# TPS6513x.net
KiCad netlist of a schematic drawn in Altium Designer
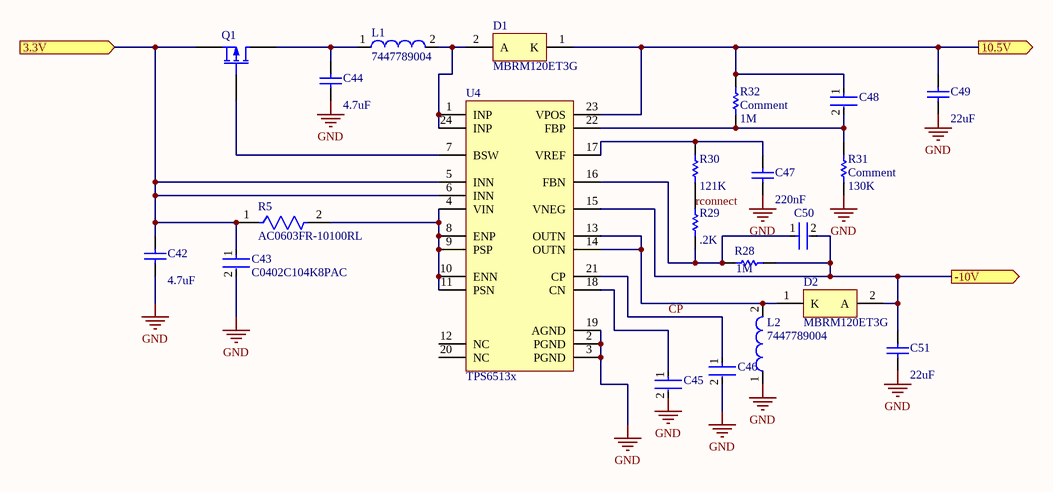
[diagram p0: TPS6513x.SchDoc]

(export (version "E")
  (design (tool "Eeschema 10.0.6"))
  (components
    (comp (ref "C42")
      (value "4.7uF")
      (footprint "4.7uF_C1206C475K3RACAUTO")
      (description "Capacitor")
      (fields (field (name "Comment") "Comment") (field (name "PUBLISHER") "Altium Limited"))
      (libsource (lib "Miscellaneous Devices") (part "Cap"))
    )
    (comp (ref "C43")
      (value "C0402C104K8PAC")
      (footprint "FP-C0402-BB-MFG")
      (description "C0402 0.10 μF X5R 10.00% 10 V")
      (fields
        (field (name "MANUFACTURER") "Kemet")
        (field (name "OCTOPART") "https://octopart.com/c0402c104k8pac-kemet-2645080")
      )
      (libsource (lib "Altium Content Vault") (part "b4654b650e69147ec39a6b967a45e02"))
    )
    (comp (ref "C44")
      (value "4.7uF")
      (footprint "4.7uF_C1206C475K3RACAUTO")
      (description "Capacitor")
      (fields (field (name "Comment") "Comment") (field (name "PUBLISHER") "Altium Limited"))
      (libsource (lib "Miscellaneous Devices") (part "Cap"))
    )
    (comp (ref "C45")
      (value "C1206C472J5GAC")
      (footprint "FP-C1206C-EB-MFG")
      (description "C1206 4,700 pF C0G 5.00% 50 V")
      (fields
        (field (name "OCTOPART") "https://octopart.com/c1206c472j5gac-kemet-1350327")
        (field (name "MANUFACTURER") "KEMET")
      )
      (libsource (lib "Altium Content Vault") (part "b4654b650e69147ec39a6b967a45e02"))
    )
    (comp (ref "C46")
      (value "C0402C103J4RAC")
      (footprint "FP-C0402-BB-MFG")
      (description "C0402 10,000 pF X7R 5.00% 16 V")
      (fields
        (field (name "TOLERANCE") "0.05")
        (field (name "OCTOPART") "https://octopart.com/c0402c103j4rac-kemet-8293494")
      )
      (libsource (lib "Altium Content Vault") (part "b4654b650e69147ec39a6b967a45e02"))
    )
    (comp (ref "C47")
      (value "220nF")
      (footprint "PCBComponent_1")
      (description "Capacitor")
      (fields (field (name "Comment") "Comment") (field (name "PUBLISHER") "Altium Limited"))
      (libsource (lib "Miscellaneous Devices") (part "Cap"))
    )
    (comp (ref "C48")
      (value "CGA1A2C0G1E6R8D030BA")
      (footprint "FP-CGA1A-0_1-0_03-IPC_B")
      (description "Cap Ceramic 6.8pF 25V C0G 0.5pF Pad SMD 0201 125°C Automotive T/R")
      (libsource (lib "Altium Content Vault") (part "b4654b650e69147ec39a6b967a45e02"))
    )
    (comp (ref "C49")
      (value "22uF")
      (footprint "Cap22uF_C1206C226M4PAC7800")
      (description "Capacitor")
      (fields (field (name "Comment") "Comment") (field (name "PUBLISHER") "Altium Limited"))
      (libsource (lib "Miscellaneous Devices") (part "Cap"))
    )
    (comp (ref "C50")
      (value "C0805C759D5GACTU")
      (footprint "FP-C0805C-DN-MFG")
      (description "CAP CER 7.5PF 50V NP0 0805")
      (fields (field (name "MANUFACTURER") "KEMET") (field (name "TOLERANCE") "0.5 pF"))
      (libsource (lib "Altium Content Vault") (part "b4654b650e69147ec39a6b967a45e02"))
    )
    (comp (ref "C51")
      (value "22uF")
      (footprint "Cap22uF_C1206C226M4PAC7800")
      (description "Capacitor")
      (fields (field (name "Comment") "Comment") (field (name "PUBLISHER") "Altium Limited"))
      (libsource (lib "Miscellaneous Devices") (part "Cap"))
    )
    (comp (ref "D1")
      (value "MBRM120ET3G")
      (footprint "ONSC-POWERMITE-2-457-04_D_V")
      (description "Schottky Power Rectifier, 2-Pin Powermite, Pb-Free, Tape and Reel")
      (fields (field (name "MANUFACTURER") "On Semiconductor"))
      (libsource (lib "") (part "ONSC-D-K1A2-2_A_1"))
    )
    (comp (ref "D2")
      (value "MBRM120ET3G")
      (footprint "ONSC-POWERMITE-2-457-04_D_V")
      (description "Schottky Power Rectifier, 2-Pin Powermite, Pb-Free, Tape and Reel")
      (fields (field (name "MANUFACTURER") "On Semiconductor"))
      (libsource (lib "Altium Content Vault") (part "ONSC-D-K1A2-2_A"))
    )
    (comp (ref "L1")
      (value "7447789004")
      (footprint "WE-PD-S-PB")
      (description "SMD-Shielded Power Inductor WE-PD, L=4.70 µH")
      (fields (field (name "MANUFACTURER") "Wuerth Elektronik"))
      (libsource (lib "Altium Content Vault") (part "PAS-IND-INDUCTOR-2"))
    )
    (comp (ref "L2")
      (value "7447789004")
      (footprint "WE-PD-S-PB")
      (description "SMD-Shielded Power Inductor WE-PD, L=4.70 µH")
      (fields (field (name "MANUFACTURER") "Wuerth Elektronik"))
      (libsource (lib "Altium Content Vault") (part "PAS-IND-INDUCTOR-2"))
    )
    (comp (ref "Q1")
      (value "Comment")
      (footprint "PCBComponent_1")
      (description "P-Channel MOSFET")
      (fields (field (name "PUBLISHER") "Altium Limited"))
      (libsource (lib "Miscellaneous Devices") (part "MOSFET-P"))
    )
    (comp (ref "R5")
      (value "AC0603FR-10100RL")
      (footprint "FP-AC0603-IPC_A")
      (description "RES 100Ω 1.00% 0.1W 0603")
      (fields (field (name "TOLERANCE") "1%"))
      (libsource (lib "Altium Content Vault") (part "1029c3af85768c4190bb7ad29bc67b5"))
    )
    (comp (ref "R28")
      (value "1M")
      (footprint "1Mohm_ESR01MZPF1004")
      (description "Resistor")
      (fields (field (name "Comment") "Comment") (field (name "PUBLISHER") "Altium Limited"))
      (libsource (lib "Miscellaneous Devices") (part "Res1"))
    )
    (comp (ref "R29")
      (value ".2K")
      (footprint "200ohm_ESR01MZPF2000")
      (description "Resistor")
      (fields (field (name "Comment") "Comment") (field (name "PUBLISHER") "Altium Limited"))
      (libsource (lib "Miscellaneous Devices") (part "Res1"))
    )
    (comp (ref "R30")
      (value "121K")
      (footprint "121k_RE0201BRE07121KL")
      (description "Resistor")
      (fields (field (name "Comment") "Comment") (field (name "PUBLISHER") "Altium Limited"))
      (libsource (lib "Miscellaneous Devices") (part "Res1"))
    )
    (comp (ref "R31")
      (value "Comment")
      (footprint "130k_RGV3216P-1303-B-T1")
      (description "Resistor")
      (fields (field (name "ALTIUM_VALUE") "130K") (field (name "PUBLISHER") "Altium Limited"))
      (libsource (lib "Miscellaneous Devices") (part "Res1"))
    )
    (comp (ref "R32")
      (value "Comment")
      (footprint "1Mohm_ESR01MZPF1004")
      (description "Resistor")
      (fields (field (name "ALTIUM_VALUE") "1M") (field (name "PUBLISHER") "Altium Limited"))
      (libsource (lib "Miscellaneous Devices") (part "Res1"))
    )
    (comp (ref "U4")
      (value "TPS6513x")
      (footprint "RGE0024B_V")
      (fields (field (name "PARTNUMBER") "TPS65130RGER") (field (name "MANUFACTURER") "Texas Instruments"))
      (libsource (lib "Altium Content Vault") (part "TI-TPS65130RGE24-2450X2450TP"))
    )
  )
  (nets
    (net (code "1") (name "/-10V") (class "Default")
      (node (ref "C50") (pin "2") (pinfunction "2_2") (pintype "passive"))
      (node (ref "C51") (pin "2") (pinfunction "2_2") (pintype "passive"))
      (node (ref "D2") (pin "2") (pinfunction "A_2") (pintype "passive"))
      (node (ref "R28") (pin "1") (pinfunction "1_1") (pintype "passive"))
      (node (ref "U4") (pin "15") (pinfunction "VNEG_15") (pintype "passive"))
    )
    (net (code "2") (name "/3.3V") (class "Default")
      (node (ref "C42") (pin "1") (pinfunction "1_1") (pintype "passive"))
      (node (ref "C43") (pin "1") (pinfunction "1_1") (pintype "passive"))
      (node (ref "Q1") (pin "3") (pinfunction "S_3") (pintype "passive"))
      (node (ref "R5") (pin "1") (pinfunction "1_1") (pintype "passive"))
      (node (ref "U4") (pin "5") (pinfunction "INN_5") (pintype "passive"))
      (node (ref "U4") (pin "6") (pinfunction "INN_6") (pintype "passive"))
    )
    (net (code "3") (name "/10.5V") (class "Default")
      (node (ref "C48") (pin "1") (pinfunction "1_1") (pintype "passive"))
      (node (ref "C49") (pin "2") (pinfunction "2_2") (pintype "passive"))
      (node (ref "D1") (pin "1") (pinfunction "K_1") (pintype "passive"))
      (node (ref "R32") (pin "2") (pinfunction "2_2") (pintype "passive"))
      (node (ref "U4") (pin "23") (pinfunction "VPOS_23") (pintype "passive"))
    )
    (net (code "4") (name "/CP") (class "Default")
      (node (ref "C46") (pin "1") (pinfunction "1_1") (pintype "passive"))
      (node (ref "U4") (pin "21") (pinfunction "CP_21") (pintype "passive"))
    )
    (net (code "6") (name "GND") (class "Default")
      (node (ref "C42") (pin "2") (pinfunction "2_2") (pintype "passive"))
      (node (ref "C43") (pin "2") (pinfunction "2_2") (pintype "passive"))
      (node (ref "C44") (pin "2") (pinfunction "2_2") (pintype "passive"))
      (node (ref "C45") (pin "2") (pinfunction "2_2") (pintype "passive"))
      (node (ref "C46") (pin "2") (pinfunction "2_2") (pintype "passive"))
      (node (ref "C47") (pin "1") (pinfunction "1_1") (pintype "passive"))
      (node (ref "C49") (pin "1") (pinfunction "1_1") (pintype "passive"))
      (node (ref "C51") (pin "1") (pinfunction "1_1") (pintype "passive"))
      (node (ref "L2") (pin "1") (pinfunction "1_1") (pintype "passive"))
      (node (ref "R31") (pin "1") (pinfunction "1_1") (pintype "passive"))
      (node (ref "U4") (pin "19") (pinfunction "AGND_19") (pintype "passive"))
      (node (ref "U4") (pin "2") (pinfunction "PGND_2") (pintype "passive"))
      (node (ref "U4") (pin "3") (pinfunction "PGND_3") (pintype "passive"))
    )
    (net (code "7") (name "Net-(D1-A)") (class "Default")
      (node (ref "D1") (pin "2") (pinfunction "A_2") (pintype "passive"))
      (node (ref "L1") (pin "2") (pinfunction "2_2") (pintype "passive"))
      (node (ref "U4") (pin "1") (pinfunction "INP_1") (pintype "passive"))
      (node (ref "U4") (pin "24") (pinfunction "INP_24") (pintype "passive"))
    )
    (net (code "8") (name "Net-(D2-K)") (class "Default")
      (node (ref "D2") (pin "1") (pinfunction "K_1") (pintype "passive"))
      (node (ref "L2") (pin "2") (pinfunction "2_2") (pintype "passive"))
      (node (ref "U4") (pin "13") (pinfunction "OUTN_13") (pintype "passive"))
      (node (ref "U4") (pin "14") (pinfunction "OUTN_14") (pintype "passive"))
    )
    (net (code "9") (name "Net-(Q1-D)") (class "Default")
      (node (ref "C44") (pin "1") (pinfunction "1_1") (pintype "passive"))
      (node (ref "L1") (pin "1") (pinfunction "1_1") (pintype "passive"))
      (node (ref "Q1") (pin "1") (pinfunction "D_1") (pintype "passive"))
    )
    (net (code "10") (name "Net-(Q1-G)") (class "Default")
      (node (ref "Q1") (pin "2") (pinfunction "G_2") (pintype "passive"))
      (node (ref "U4") (pin "7") (pinfunction "BSW_7") (pintype "passive"))
    )
    (net (code "11") (name "Net-(R29-Pad2)") (class "Default")
      (node (ref "R29") (pin "2") (pinfunction "2_2") (pintype "passive"))
      (node (ref "R30") (pin "1") (pinfunction "1_1") (pintype "passive"))
    )
    (net (code "12") (name "Net-(U4-CN)") (class "Default")
      (node (ref "C45") (pin "1") (pinfunction "1_1") (pintype "passive"))
      (node (ref "U4") (pin "18") (pinfunction "CN_18") (pintype "passive"))
    )
    (net (code "13") (name "Net-(U4-ENN)") (class "Default")
      (node (ref "R5") (pin "2") (pinfunction "2_2") (pintype "passive"))
      (node (ref "U4") (pin "10") (pinfunction "ENN_10") (pintype "passive"))
      (node (ref "U4") (pin "11") (pinfunction "PSN_11") (pintype "passive"))
      (node (ref "U4") (pin "4") (pinfunction "VIN_4") (pintype "passive"))
      (node (ref "U4") (pin "8") (pinfunction "ENP_8") (pintype "passive"))
      (node (ref "U4") (pin "9") (pinfunction "PSP_9") (pintype "passive"))
    )
    (net (code "14") (name "Net-(U4-FBN)") (class "Default")
      (node (ref "C50") (pin "1") (pinfunction "1_1") (pintype "passive"))
      (node (ref "R28") (pin "2") (pinfunction "2_2") (pintype "passive"))
      (node (ref "R29") (pin "1") (pinfunction "1_1") (pintype "passive"))
      (node (ref "U4") (pin "16") (pinfunction "FBN_16") (pintype "passive"))
    )
    (net (code "15") (name "Net-(U4-FBP)") (class "Default")
      (node (ref "C48") (pin "2") (pinfunction "2_2") (pintype "passive"))
      (node (ref "R31") (pin "2") (pinfunction "2_2") (pintype "passive"))
      (node (ref "R32") (pin "1") (pinfunction "1_1") (pintype "passive"))
      (node (ref "U4") (pin "22") (pinfunction "FBP_22") (pintype "passive"))
    )
    (net (code "16") (name "Net-(U4-VREF)") (class "Default")
      (node (ref "C47") (pin "2") (pinfunction "2_2") (pintype "passive"))
      (node (ref "R30") (pin "2") (pinfunction "2_2") (pintype "passive"))
      (node (ref "U4") (pin "17") (pinfunction "VREF_17") (pintype "passive"))
    )
    (net (code "17") (name "unconnected-(U4-NC-Pad12)") (class "Default")
      (node (ref "U4") (pin "12") (pinfunction "NC_12") (pintype "passive"))
    )
    (net (code "18") (name "unconnected-(U4-NC-Pad20)") (class "Default")
      (node (ref "U4") (pin "20") (pinfunction "NC_20") (pintype "passive"))
    )
  )
)
